# Comm.net
KiCad netlist of a schematic drawn in Altium Designer
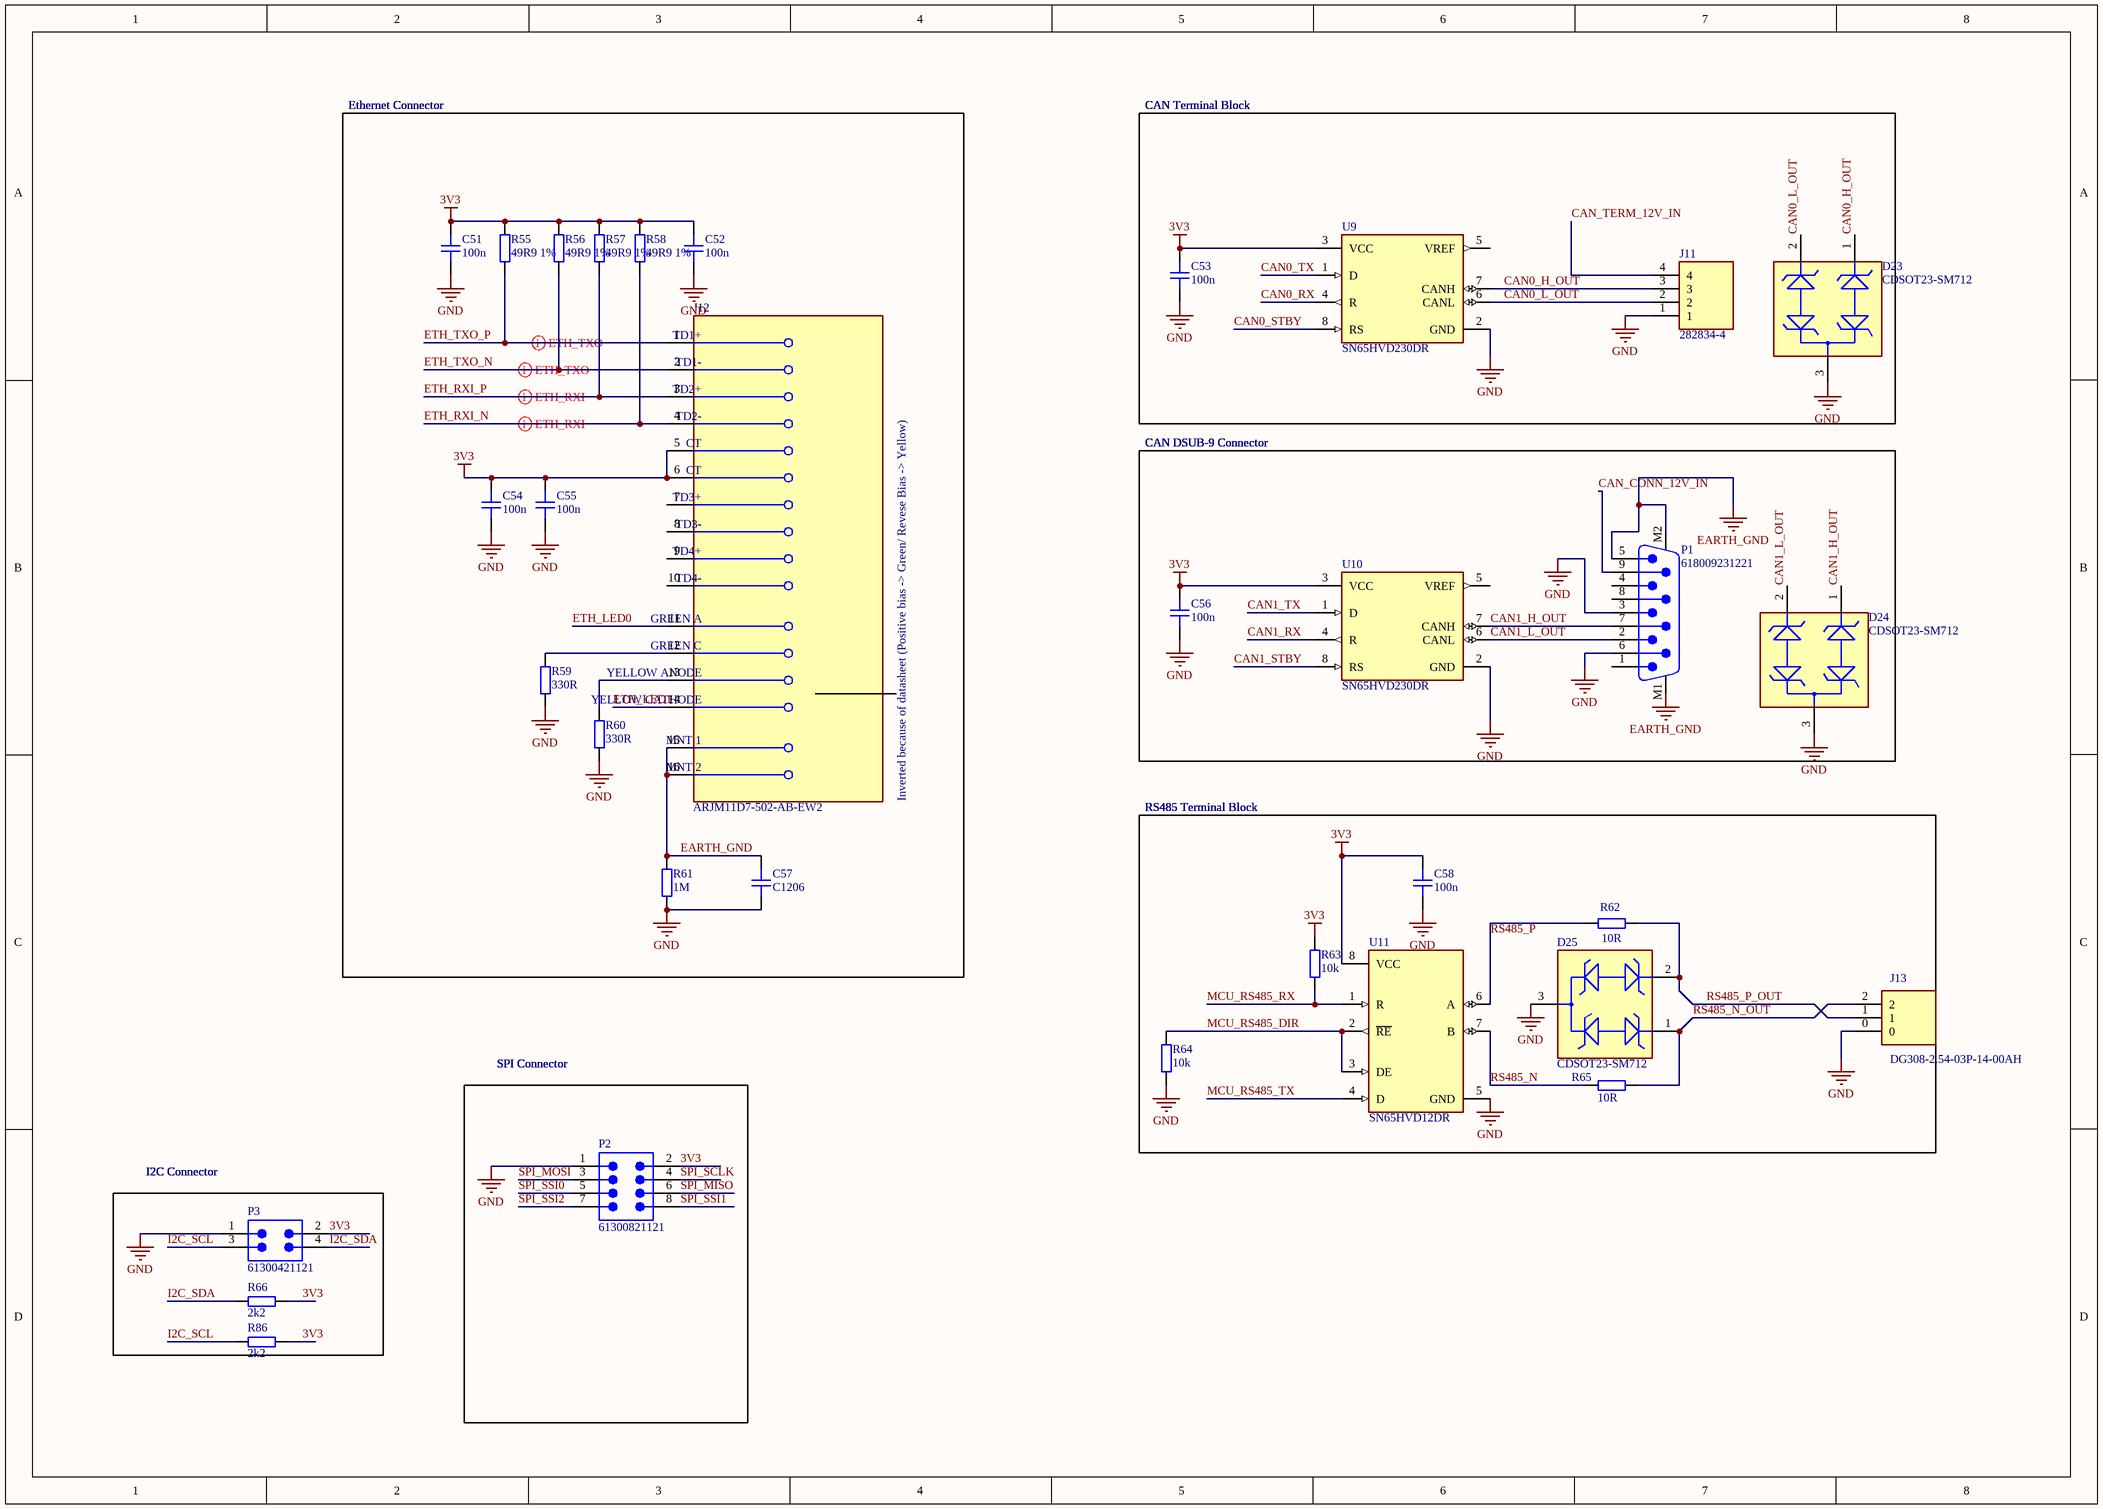
[diagram p0: Comm.SchDoc]

(export (version "E")
  (design (tool "Eeschema 10.0.6"))
  (components
    (comp (ref "C51")
      (value "100n")
      (footprint "CAP_0402")
      (description "Capacitor SMD 0402")
      (libsource (lib "Schematic-Lib-PhilsLab") (part "CAP_0402"))
    )
    (comp (ref "C52")
      (value "100n")
      (footprint "CAP_0402")
      (description "Capacitor SMD 0402")
      (libsource (lib "Schematic-Lib-PhilsLab") (part "CAP_0402"))
    )
    (comp (ref "C53")
      (value "100n")
      (footprint "CAP_0402")
      (description "Capacitor SMD 0402")
      (libsource (lib "Schematic-Lib-PhilsLab") (part "CAP_0402"))
    )
    (comp (ref "C54")
      (value "100n")
      (footprint "CAP_0402")
      (description "Capacitor SMD 0402")
      (libsource (lib "Schematic-Lib-PhilsLab") (part "CAP_0402"))
    )
    (comp (ref "C55")
      (value "100n")
      (footprint "CAP_0402")
      (description "Capacitor SMD 0402")
      (libsource (lib "Schematic-Lib-PhilsLab") (part "CAP_0402"))
    )
    (comp (ref "C56")
      (value "100n")
      (footprint "CAP_0402")
      (description "Capacitor SMD 0402")
      (libsource (lib "Schematic-Lib-PhilsLab") (part "CAP_0402"))
    )
    (comp (ref "C57")
      (value "C1206")
      (footprint "CAP_1206")
      (description "4700pF 2kV")
      (libsource (lib "Schematic-Lib-PhilsLab") (part "CAP_1206"))
    )
    (comp (ref "C58")
      (value "100n")
      (footprint "CAP_0402")
      (description "Capacitor SMD 0402")
      (libsource (lib "Schematic-Lib-PhilsLab") (part "CAP_0402"))
    )
    (comp (ref "D23")
      (value "CDSOT23-SM712")
      (footprint "FP-SOT23-MFG")
      (description "TVS DIODE 7V/12V 14V/26V SOT23-3")
      (fields
        (field (name "MANUFACTURER") "Bourns Inc.")
        (field (name "OCTOPART") "https://octopart.com/cdsot23-sm712-bourns-7576327")
      )
      (libsource (lib "Altium Content Vault") (part "81303f94231262926866863442dad16"))
    )
    (comp (ref "D24")
      (value "CDSOT23-SM712")
      (footprint "FP-SOT23-MFG")
      (description "TVS DIODE 7V/12V 14V/26V SOT23-3")
      (fields
        (field (name "MANUFACTURER") "Bourns Inc.")
        (field (name "OCTOPART") "https://octopart.com/cdsot23-sm712-bourns-7576327")
      )
      (libsource (lib "Altium Content Vault") (part "81303f94231262926866863442dad16"))
    )
    (comp (ref "D25")
      (value "CDSOT23-SM712")
      (footprint "FP-SOT23-MFG")
      (description "TVS DIODE 7V/12V 14V/26V SOT23-3")
      (fields
        (field (name "MANUFACTURER") "Bourns Inc.")
        (field (name "OCTOPART") "https://octopart.com/cdsot23-sm712-bourns-7576327")
      )
      (libsource (lib "Altium Content Vault") (part "81303f94231262926866863442dad16"))
    )
    (comp (ref "J11")
      (value "282834-4")
      (footprint "TE_282834-4")
      (description "4 Position Wire to Board Terminal Block Horizontal with Board 0.100 (2.54mm) Through Hole")
      (fields (field (name "MF") "TE Connectivity"))
      (libsource (lib "282834-4") (part "282834-4"))
    )
    (comp (ref "J12")
      (value "ARJM11D7-502-AB-EW2")
      (footprint "FP-ARJM11D7-502-AB-EW2-MFG")
      (description "CONN JACK 1PORT 1000 BASE-T PCB")
      (libsource (lib "Altium Content Vault") (part "be7db50d5dbc4a89f401f51284e3e2c"))
    )
    (comp (ref "J13")
      (value "DG308-2.54-03P-14-00AH")
      (footprint "DG308-2.54-03P-14-00AH-Footprint-1")
      (description "2.54mm PCB Terminal Block Angled 90 Degree")
      (libsource (lib "DIGI2") (part "DG308-2.54-03P-14-00AH-Symbol-1"))
    )
    (comp (ref "P1")
      (value "618009231221")
      (footprint "618009231221")
      (libsource (lib "Altium Content Vault") (part "D-Sub_Male_09p"))
    )
    (comp (ref "P2")
      (value "61300821121")
      (footprint "61300821121")
      (libsource (lib "Altium Content Vault") (part "Header_Male_2R_08P"))
    )
    (comp (ref "P3")
      (value "61300421121")
      (footprint "61300421121")
      (libsource (lib "Altium Content Vault") (part "Header_Male_2R_04P"))
    )
    (comp (ref "R55")
      (value "49R9 1%")
      (footprint "RES_0402")
      (description "Resistor SMD 0402")
      (libsource (lib "Schematic-Lib-PhilsLab") (part "RES_0402"))
    )
    (comp (ref "R56")
      (value "49R9 1%")
      (footprint "RES_0402")
      (description "Resistor SMD 0402")
      (libsource (lib "Schematic-Lib-PhilsLab") (part "RES_0402"))
    )
    (comp (ref "R57")
      (value "49R9 1%")
      (footprint "RES_0402")
      (description "Resistor SMD 0402")
      (libsource (lib "Schematic-Lib-PhilsLab") (part "RES_0402"))
    )
    (comp (ref "R58")
      (value "49R9 1%")
      (footprint "RES_0402")
      (description "Resistor SMD 0402")
      (libsource (lib "Schematic-Lib-PhilsLab") (part "RES_0402"))
    )
    (comp (ref "R59")
      (value "330R")
      (footprint "RES_0402")
      (description "Resistor SMD 0402")
      (libsource (lib "Schematic-Lib-PhilsLab") (part "RES_0402"))
    )
    (comp (ref "R60")
      (value "330R")
      (footprint "RES_0402")
      (description "Resistor SMD 0402")
      (libsource (lib "Schematic-Lib-PhilsLab") (part "RES_0402"))
    )
    (comp (ref "R61")
      (value "1M")
      (footprint "RES_0402")
      (description "Resistor SMD 0402")
      (libsource (lib "Schematic-Lib-PhilsLab") (part "RES_0402"))
    )
    (comp (ref "R62")
      (value "10R")
      (footprint "RES_0603")
      (description "Resistor SMD 0603")
      (libsource (lib "Schematic-Lib-PhilsLab") (part "RES_0603"))
    )
    (comp (ref "R63")
      (value "10k")
      (footprint "RES_0402")
      (description "Resistor SMD 0402")
      (libsource (lib "Schematic-Lib-PhilsLab") (part "RES_0402"))
    )
    (comp (ref "R64")
      (value "10k")
      (footprint "RES_0402")
      (description "Resistor SMD 0402")
      (libsource (lib "Schematic-Lib-PhilsLab") (part "RES_0402"))
    )
    (comp (ref "R65")
      (value "10R")
      (footprint "RES_0603")
      (description "Resistor SMD 0603")
      (libsource (lib "Schematic-Lib-PhilsLab") (part "RES_0603"))
    )
    (comp (ref "R66")
      (value "2k2")
      (footprint "RES_0402")
      (description "Resistor SMD 0402")
      (libsource (lib "Schematic-Lib-PhilsLab") (part "RES_0402"))
    )
    (comp (ref "R86")
      (value "2k2")
      (footprint "RES_0402")
      (description "Resistor SMD 0402")
      (libsource (lib "Schematic-Lib-PhilsLab") (part "RES_0402"))
    )
    (comp (ref "U9")
      (value "SN65HVD230DR")
      (footprint "FP-D0008A-IPC_A")
      (description "IC TRANSCEIVER HALF 1/1 8SOIC")
      (libsource (lib "Altium Content Vault") (part "43b56812b1adf0e60a7acfb7c27ab91"))
    )
    (comp (ref "U10")
      (value "SN65HVD230DR")
      (footprint "FP-D0008A-IPC_A")
      (description "IC TRANSCEIVER HALF 1/1 8SOIC")
      (libsource (lib "Altium Content Vault") (part "43b56812b1adf0e60a7acfb7c27ab91"))
    )
    (comp (ref "U11")
      (value "SN65HVD12DR")
      (footprint "FP-D0008A-MFG")
      (description "IC TRANSCEIVER HALF 1/1 8SOIC")
      (fields
        (field (name "OCTOPART") "https://octopart.com/sn65hvd12dr-texas+instruments-713591")
        (field (name "MANUFACTURER") "Texas Instruments")
      )
      (libsource (lib "Altium Content Vault") (part "9b5e85850bc5e2b73de6fccf45375aa"))
    )
  )
  (nets
    (net (code "1") (name "/CAN0_H_OUT") (class "Default")
      (node (ref "D23") (pin "1") (pinfunction "1_1") (pintype "passive"))
      (node (ref "J11") (pin "3") (pinfunction "3_3") (pintype "passive"))
      (node (ref "U9") (pin "7") (pinfunction "CANH_7") (pintype "bidirectional"))
    )
    (net (code "2") (name "/CAN0_L_OUT") (class "Default")
      (node (ref "D23") (pin "2") (pinfunction "2_2") (pintype "passive"))
      (node (ref "J11") (pin "2") (pinfunction "2_2") (pintype "passive"))
      (node (ref "U9") (pin "6") (pinfunction "CANL_6") (pintype "bidirectional"))
    )
    (net (code "3") (name "/CAN0_RX") (class "Default")
      (node (ref "U9") (pin "4") (pinfunction "R_4") (pintype "output"))
    )
    (net (code "4") (name "/CAN0_STBY") (class "Default")
      (node (ref "U9") (pin "8") (pinfunction "RS_8") (pintype "input"))
    )
    (net (code "5") (name "/CAN0_TX") (class "Default")
      (node (ref "U9") (pin "1") (pinfunction "D_1") (pintype "input"))
    )
    (net (code "6") (name "/CAN1_H_OUT") (class "Default")
      (node (ref "D24") (pin "1") (pinfunction "1_1") (pintype "passive"))
      (node (ref "P1") (pin "7") (pinfunction "7_7") (pintype "passive"))
      (node (ref "U10") (pin "7") (pinfunction "CANH_7") (pintype "bidirectional"))
    )
    (net (code "7") (name "/CAN1_L_OUT") (class "Default")
      (node (ref "D24") (pin "2") (pinfunction "2_2") (pintype "passive"))
      (node (ref "P1") (pin "2") (pinfunction "2_2") (pintype "passive"))
      (node (ref "U10") (pin "6") (pinfunction "CANL_6") (pintype "bidirectional"))
    )
    (net (code "8") (name "/CAN1_RX") (class "Default")
      (node (ref "U10") (pin "4") (pinfunction "R_4") (pintype "output"))
    )
    (net (code "9") (name "/CAN1_STBY") (class "Default")
      (node (ref "U10") (pin "8") (pinfunction "RS_8") (pintype "input"))
    )
    (net (code "10") (name "/CAN1_TX") (class "Default")
      (node (ref "U10") (pin "1") (pinfunction "D_1") (pintype "input"))
    )
    (net (code "11") (name "/CAN_CONN_12V_IN") (class "Default")
      (node (ref "P1") (pin "9") (pinfunction "9_9") (pintype "passive"))
    )
    (net (code "12") (name "/CAN_TERM_12V_IN") (class "Default")
      (node (ref "J11") (pin "4") (pinfunction "4_4") (pintype "passive"))
    )
    (net (code "13") (name "/ETH_LED0") (class "Default")
      (node (ref "J12") (pin "11") (pinfunction "GREEN_A_11") (pintype "passive"))
    )
    (net (code "14") (name "/ETH_LED1") (class "Default")
      (node (ref "J12") (pin "14") (pinfunction "YELLOW_CATHODE_14") (pintype "passive"))
    )
    (net (code "15") (name "/ETH_RXI_N") (class "Default")
      (node (ref "J12") (pin "4") (pinfunction "TD2-_4") (pintype "passive"))
      (node (ref "R58") (pin "1") (pinfunction "1_1") (pintype "passive"))
    )
    (net (code "16") (name "/ETH_RXI_P") (class "Default")
      (node (ref "J12") (pin "3") (pinfunction "TD2+_3") (pintype "passive"))
      (node (ref "R57") (pin "1") (pinfunction "1_1") (pintype "passive"))
    )
    (net (code "17") (name "/ETH_TXO_N") (class "Default")
      (node (ref "J12") (pin "2") (pinfunction "TD1-_2") (pintype "passive"))
      (node (ref "R56") (pin "1") (pinfunction "1_1") (pintype "passive"))
    )
    (net (code "18") (name "/ETH_TXO_P") (class "Default")
      (node (ref "J12") (pin "1") (pinfunction "TD1+_1") (pintype "passive"))
      (node (ref "R55") (pin "1") (pinfunction "1_1") (pintype "passive"))
    )
    (net (code "19") (name "/I2C_SCL") (class "Default")
      (node (ref "P3") (pin "3") (pinfunction "3_3") (pintype "passive"))
      (node (ref "R86") (pin "2") (pinfunction "2_2") (pintype "passive"))
    )
    (net (code "20") (name "/I2C_SDA") (class "Default")
      (node (ref "P3") (pin "4") (pinfunction "4_4") (pintype "passive"))
      (node (ref "R66") (pin "2") (pinfunction "2_2") (pintype "passive"))
    )
    (net (code "21") (name "/MCU_RS485_DIR") (class "Default")
      (node (ref "R64") (pin "2") (pinfunction "2_2") (pintype "passive"))
      (node (ref "U11") (pin "2") (pinfunction "~{RE}_2") (pintype "output"))
      (node (ref "U11") (pin "3") (pinfunction "DE_3") (pintype "input"))
    )
    (net (code "22") (name "/MCU_RS485_RX") (class "Default")
      (node (ref "R63") (pin "1") (pinfunction "1_1") (pintype "passive"))
      (node (ref "U11") (pin "1") (pinfunction "R_1") (pintype "input"))
    )
    (net (code "23") (name "/MCU_RS485_TX") (class "Default")
      (node (ref "U11") (pin "4") (pinfunction "D_4") (pintype "input"))
    )
    (net (code "24") (name "/RS485_N") (class "Default")
      (node (ref "R65") (pin "1") (pinfunction "1_1") (pintype "passive"))
      (node (ref "U11") (pin "7") (pinfunction "B_7") (pintype "bidirectional"))
    )
    (net (code "25") (name "/RS485_N_OUT") (class "Default")
      (node (ref "D25") (pin "1") (pinfunction "1_1") (pintype "passive"))
      (node (ref "J13") (pin "2") (pinfunction "2_2") (pintype "passive"))
      (node (ref "R65") (pin "2") (pinfunction "2_2") (pintype "passive"))
    )
    (net (code "26") (name "/RS485_P") (class "Default")
      (node (ref "R62") (pin "1") (pinfunction "1_1") (pintype "passive"))
      (node (ref "U11") (pin "6") (pinfunction "A_6") (pintype "bidirectional"))
    )
    (net (code "27") (name "/RS485_P_OUT") (class "Default")
      (node (ref "D25") (pin "2") (pinfunction "2_2") (pintype "passive"))
      (node (ref "J13") (pin "1") (pinfunction "1_1") (pintype "passive"))
      (node (ref "R62") (pin "2") (pinfunction "2_2") (pintype "passive"))
    )
    (net (code "28") (name "/SPI_MISO") (class "Default")
      (node (ref "P2") (pin "6") (pinfunction "6_6") (pintype "passive"))
    )
    (net (code "29") (name "/SPI_MOSI") (class "Default")
      (node (ref "P2") (pin "3") (pinfunction "3_3") (pintype "passive"))
    )
    (net (code "30") (name "/SPI_SCLK") (class "Default")
      (node (ref "P2") (pin "4") (pinfunction "4_4") (pintype "passive"))
    )
    (net (code "31") (name "/SPI_SSI0") (class "Default")
      (node (ref "P2") (pin "5") (pinfunction "5_5") (pintype "passive"))
    )
    (net (code "32") (name "/SPI_SSI1") (class "Default")
      (node (ref "P2") (pin "8") (pinfunction "8_8") (pintype "passive"))
    )
    (net (code "33") (name "/SPI_SSI2") (class "Default")
      (node (ref "P2") (pin "7") (pinfunction "7_7") (pintype "passive"))
    )
    (net (code "34") (name "3V3") (class "Default")
      (node (ref "C51") (pin "2") (pinfunction "2_2") (pintype "passive"))
      (node (ref "C52") (pin "2") (pinfunction "2_2") (pintype "passive"))
      (node (ref "C53") (pin "2") (pinfunction "2_2") (pintype "passive"))
      (node (ref "C54") (pin "2") (pinfunction "2_2") (pintype "passive"))
      (node (ref "C55") (pin "2") (pinfunction "2_2") (pintype "passive"))
      (node (ref "C56") (pin "2") (pinfunction "2_2") (pintype "passive"))
      (node (ref "C58") (pin "2") (pinfunction "2_2") (pintype "passive"))
      (node (ref "J12") (pin "5") (pinfunction "CT_5") (pintype "passive"))
      (node (ref "J12") (pin "6") (pinfunction "CT_6") (pintype "passive"))
      (node (ref "P2") (pin "2") (pinfunction "2_2") (pintype "passive"))
      (node (ref "P3") (pin "2") (pinfunction "2_2") (pintype "passive"))
      (node (ref "R55") (pin "2") (pinfunction "2_2") (pintype "passive"))
      (node (ref "R56") (pin "2") (pinfunction "2_2") (pintype "passive"))
      (node (ref "R57") (pin "2") (pinfunction "2_2") (pintype "passive"))
      (node (ref "R58") (pin "2") (pinfunction "2_2") (pintype "passive"))
      (node (ref "R63") (pin "2") (pinfunction "2_2") (pintype "passive"))
      (node (ref "R66") (pin "1") (pinfunction "1_1") (pintype "passive"))
      (node (ref "R86") (pin "1") (pinfunction "1_1") (pintype "passive"))
      (node (ref "U10") (pin "3") (pinfunction "VCC_3") (pintype "power_in"))
      (node (ref "U11") (pin "8") (pinfunction "VCC_8") (pintype "power_in"))
      (node (ref "U9") (pin "3") (pinfunction "VCC_3") (pintype "power_in"))
    )
    (net (code "35") (name "EARTH_GND") (class "Default")
      (node (ref "C57") (pin "2") (pinfunction "2_2") (pintype "passive"))
      (node (ref "J12") (pin "15") (pinfunction "MNT_1_15") (pintype "passive"))
      (node (ref "J12") (pin "16") (pinfunction "MNT_2_16") (pintype "passive"))
      (node (ref "P1") (pin "5") (pinfunction "5_5") (pintype "passive"))
      (node (ref "P1") (pin "M1") (pinfunction "M1_M1") (pintype "passive"))
      (node (ref "P1") (pin "M2") (pinfunction "M2_M2") (pintype "passive"))
      (node (ref "R61") (pin "2") (pinfunction "2_2") (pintype "passive"))
    )
    (net (code "36") (name "GND") (class "Default")
      (node (ref "C51") (pin "1") (pinfunction "1_1") (pintype "passive"))
      (node (ref "C52") (pin "1") (pinfunction "1_1") (pintype "passive"))
      (node (ref "C53") (pin "1") (pinfunction "1_1") (pintype "passive"))
      (node (ref "C54") (pin "1") (pinfunction "1_1") (pintype "passive"))
      (node (ref "C55") (pin "1") (pinfunction "1_1") (pintype "passive"))
      (node (ref "C56") (pin "1") (pinfunction "1_1") (pintype "passive"))
      (node (ref "C57") (pin "1") (pinfunction "1_1") (pintype "passive"))
      (node (ref "C58") (pin "1") (pinfunction "1_1") (pintype "passive"))
      (node (ref "D23") (pin "3") (pinfunction "3_3") (pintype "passive"))
      (node (ref "D24") (pin "3") (pinfunction "3_3") (pintype "passive"))
      (node (ref "D25") (pin "3") (pinfunction "3_3") (pintype "passive"))
      (node (ref "J11") (pin "1") (pinfunction "1_1") (pintype "passive"))
      (node (ref "J13") (pin "0") (pinfunction "0_0") (pintype "passive"))
      (node (ref "P1") (pin "3") (pinfunction "3_3") (pintype "passive"))
      (node (ref "P1") (pin "6") (pinfunction "6_6") (pintype "passive"))
      (node (ref "P2") (pin "1") (pinfunction "1_1") (pintype "passive"))
      (node (ref "P3") (pin "1") (pinfunction "1_1") (pintype "passive"))
      (node (ref "R59") (pin "1") (pinfunction "1_1") (pintype "passive"))
      (node (ref "R60") (pin "1") (pinfunction "1_1") (pintype "passive"))
      (node (ref "R61") (pin "1") (pinfunction "1_1") (pintype "passive"))
      (node (ref "R64") (pin "1") (pinfunction "1_1") (pintype "passive"))
      (node (ref "U10") (pin "2") (pinfunction "GND_2") (pintype "power_in"))
      (node (ref "U11") (pin "5") (pinfunction "GND_5") (pintype "power_in"))
      (node (ref "U9") (pin "2") (pinfunction "GND_2") (pintype "power_in"))
    )
    (net (code "37") (name "Net-(J12-GREEN_C)") (class "Default")
      (node (ref "J12") (pin "12") (pinfunction "GREEN_C_12") (pintype "passive"))
      (node (ref "R59") (pin "2") (pinfunction "2_2") (pintype "passive"))
    )
    (net (code "38") (name "Net-(J12-YELLOW_ANODE)") (class "Default")
      (node (ref "J12") (pin "13") (pinfunction "YELLOW_ANODE_13") (pintype "passive"))
      (node (ref "R60") (pin "2") (pinfunction "2_2") (pintype "passive"))
    )
    (net (code "39") (name "unconnected-(J12-TD3+-Pad7)") (class "Default")
      (node (ref "J12") (pin "7") (pinfunction "TD3+_7") (pintype "passive"))
    )
    (net (code "40") (name "unconnected-(J12-TD3--Pad8)") (class "Default")
      (node (ref "J12") (pin "8") (pinfunction "TD3-_8") (pintype "passive"))
    )
    (net (code "41") (name "unconnected-(J12-TD4+-Pad9)") (class "Default")
      (node (ref "J12") (pin "9") (pinfunction "TD4+_9") (pintype "passive"))
    )
    (net (code "42") (name "unconnected-(J12-TD4--Pad10)") (class "Default")
      (node (ref "J12") (pin "10") (pinfunction "TD4-_10") (pintype "passive"))
    )
    (net (code "43") (name "unconnected-(P1-Pad1)") (class "Default")
      (node (ref "P1") (pin "1") (pinfunction "1_1") (pintype "passive"))
    )
    (net (code "44") (name "unconnected-(P1-Pad4)") (class "Default")
      (node (ref "P1") (pin "4") (pinfunction "4_4") (pintype "passive"))
    )
    (net (code "45") (name "unconnected-(P1-Pad8)") (class "Default")
      (node (ref "P1") (pin "8") (pinfunction "8_8") (pintype "passive"))
    )
    (net (code "46") (name "unconnected-(U9-VREF-Pad5)") (class "Default")
      (node (ref "U9") (pin "5") (pinfunction "VREF_5") (pintype "output"))
    )
    (net (code "47") (name "unconnected-(U10-VREF-Pad5)") (class "Default")
      (node (ref "U10") (pin "5") (pinfunction "VREF_5") (pintype "output"))
    )
  )
)
